# CC-S07-V00-AnalogueIn.net
KiCad netlist of a schematic drawn in Altium Designer
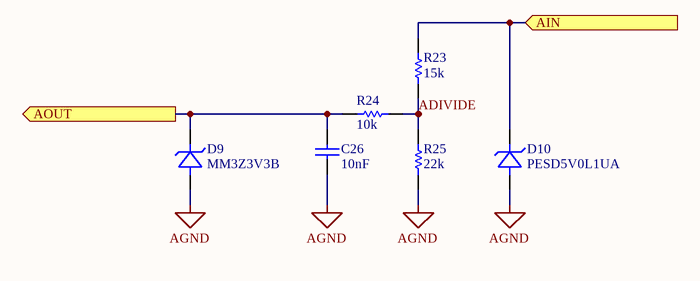
[diagram p0: CC-S07-V00-AnalogueIn.SchDoc]

(export (version "E")
  (design (tool "Eeschema 10.0.6"))
  (components
    (comp (ref "C26")
      (value "10nF")
      (footprint "Cap_Ceramic_0603")
      (description "Capacitor, Ceramic, SMD, 10nF, 50V, 5%, X7R, 0603")
      (libsource (lib "StandardCapacitors") (part "10nF 50V 5% X7R 0603"))
    )
    (comp (ref "D9")
      (value "MM3Z3V3B")
      (footprint "SOD323F")
      (description "Diode, SMD, Zenner, 3.3V, 2%, 410mW, SOD-323F")
      (libsource (lib "QUTMS_DiodeLibrary") (part "MM3Z3V3B"))
    )
    (comp (ref "D10")
      (value "PESD5V0L1UA")
      (footprint "SOD323F")
      (description "12V Clamp 3.5A (8/20µs) Ipp Tvs Diode Surface Mount SOD-323")
      (libsource (lib "QUTMS_DiodeLibrary") (part "PESD5V0L1UA"))
    )
    (comp (ref "R23")
      (value "15k")
      (footprint "Res_ThinFilm_0603")
      (description "Resistor, SMD, 15k, 0.1W, 5%, 0603")
      (libsource (lib "StandardResistors") (part "15k 5% 0603"))
    )
    (comp (ref "R24")
      (value "10k")
      (footprint "Res_ThinFilm_0603")
      (description "Resistor, SMD, 10k, 0.1W, 5%, 0603")
      (libsource (lib "StandardResistors") (part "10k 5% 0603"))
    )
    (comp (ref "R25")
      (value "22k")
      (footprint "Res_ThinFilm_0603")
      (description "Resistor, SMD, 22k, 0.1W, 5%, 0603")
      (libsource (lib "StandardResistors") (part "22k 5% 0603"))
    )
  )
  (nets
    (net (code "1") (name "/ADIVIDE") (class "Default")
      (node (ref "R23") (pin "1") (pinfunction "1_1") (pintype "passive"))
      (node (ref "R24") (pin "2") (pinfunction "2_2") (pintype "passive"))
      (node (ref "R25") (pin "2") (pinfunction "2_2") (pintype "passive"))
    )
    (net (code "2") (name "/AIN") (class "Default")
      (node (ref "D10") (pin "K") (pinfunction "Cathode_K") (pintype "passive"))
      (node (ref "R23") (pin "2") (pinfunction "2_2") (pintype "passive"))
    )
    (net (code "3") (name "/AOUT") (class "Default")
      (node (ref "C26") (pin "2") (pinfunction "2_2") (pintype "passive"))
      (node (ref "D9") (pin "K") (pinfunction "Cathode_K") (pintype "passive"))
      (node (ref "R24") (pin "1") (pinfunction "1_1") (pintype "passive"))
    )
    (net (code "4") (name "AGND") (class "Default")
      (node (ref "C26") (pin "1") (pinfunction "1_1") (pintype "passive"))
      (node (ref "D10") (pin "A") (pinfunction "Anode_A") (pintype "passive"))
      (node (ref "D9") (pin "A") (pinfunction "Anode_A") (pintype "passive"))
      (node (ref "R25") (pin "1") (pinfunction "1_1") (pintype "passive"))
    )
  )
)
